# RS232_IrDA.net
KiCad netlist of a schematic drawn in Altium Designer
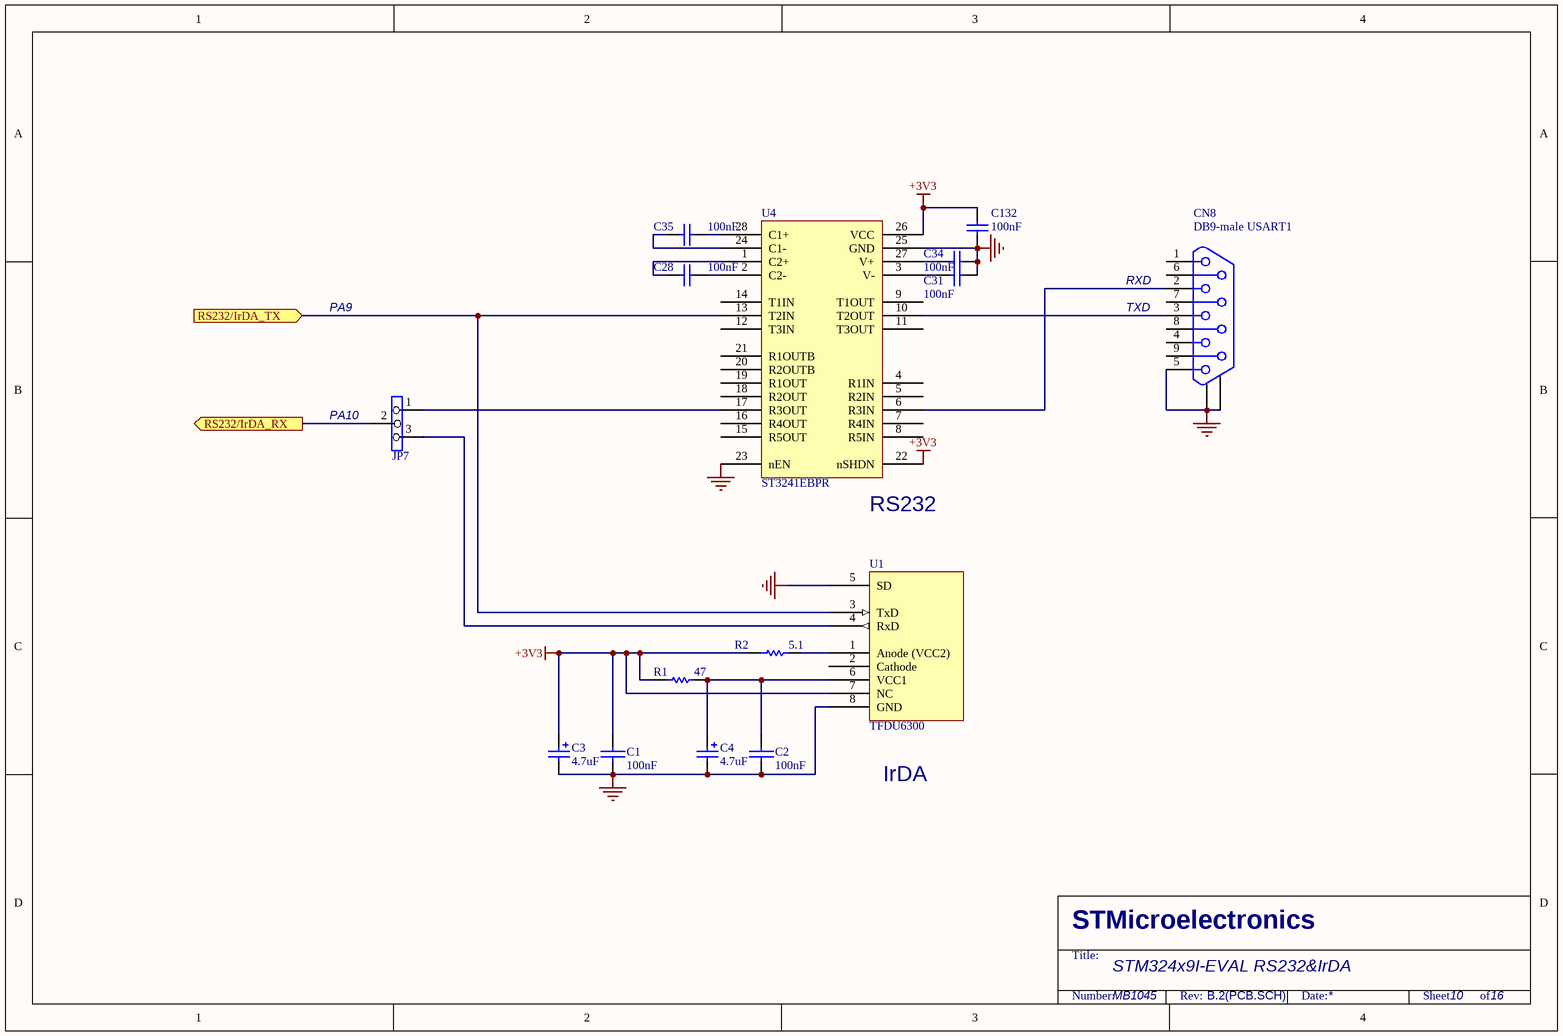
[diagram p0: RS232&IrDA.SchDoc]

(export (version "E")
  (design (tool "Eeschema 10.0.6"))
  (components
    (comp (ref "C1")
      (value "100nF")
      (footprint "0603C")
      (description "Capacitor")
      (libsource (lib "*") (part "CAP"))
    )
    (comp (ref "C2")
      (value "100nF")
      (footprint "0603C")
      (description "Capacitor")
      (libsource (lib "*") (part "CAP"))
    )
    (comp (ref "C3")
      (value "4.7uF")
      (footprint "TAN-A")
      (description "Polarized Capacitor (Radial)")
      (fields (field (name "PUBLISHER") "Altium Limited"))
      (libsource (lib "Miscellaneous Devices") (part "Cap Pol1"))
    )
    (comp (ref "C4")
      (value "4.7uF")
      (footprint "TAN-A")
      (description "Polarized Capacitor (Radial)")
      (fields (field (name "PUBLISHER") "Altium Limited"))
      (libsource (lib "Miscellaneous Devices") (part "Cap Pol1"))
    )
    (comp (ref "C28")
      (value "100nF")
      (footprint "0603C")
      (description "Capacitor")
      (fields (field (name "PUBLISHER") "Altium Limited"))
      (libsource (lib "Miscellaneous Devices") (part "Cap"))
    )
    (comp (ref "C31")
      (value "100nF")
      (footprint "0603C")
      (description "Capacitor")
      (fields (field (name "PUBLISHER") "Altium Limited"))
      (libsource (lib "Miscellaneous Devices") (part "Cap"))
    )
    (comp (ref "C34")
      (value "100nF")
      (footprint "0603C")
      (description "Capacitor")
      (fields (field (name "PUBLISHER") "Altium Limited"))
      (libsource (lib "Miscellaneous Devices") (part "Cap"))
    )
    (comp (ref "C35")
      (value "100nF")
      (footprint "0603C")
      (description "Capacitor")
      (fields (field (name "PUBLISHER") "Altium Limited"))
      (libsource (lib "Miscellaneous Devices") (part "Cap"))
    )
    (comp (ref "C132")
      (value "100nF")
      (footprint "0603C")
      (description "Capacitor")
      (fields (field (name "PUBLISHER") "Altium Limited"))
      (libsource (lib "Miscellaneous Devices") (part "Cap"))
    )
    (comp (ref "CN8")
      (value "DB9-male USART1")
      (footprint "DB9/M")
      (libsource (lib "mb1045") (part "DB9-USART"))
    )
    (comp (ref "JP7") (value "~") (footprint "SIP3") (libsource (lib "STR910_SCHLIB") (part "Jumper3")))
    (comp (ref "R1")
      (value "47")
      (footprint "0603R")
      (description "Resistor")
      (fields (field (name "PUBLISHER") "Altium Limited"))
      (libsource (lib "Miscellaneous Devices") (part "Res1"))
    )
    (comp (ref "R2")
      (value "5.1")
      (footprint "0603R")
      (description "Resistor")
      (fields (field (name "PUBLISHER") "Altium Limited"))
      (libsource (lib "Miscellaneous Devices") (part "Res1"))
    )
    (comp (ref "U1")
      (value "TFDU6300")
      (footprint "IR_VISHAY3")
      (description "TFDU4300")
      (libsource (lib "*") (part "TFDU4300"))
    )
    (comp (ref "U4")
      (value "ST3241EBPR")
      (footprint "SSOP28_0R65_10R2X7R8")
      (libsource (lib "*") (part "ST3241"))
    )
  )
  (nets
    (net (code "1") (name "+3V3") (class "Default")
      (node (ref "C1") (pin "1") (pinfunction "1_1") (pintype "passive"))
      (node (ref "C132") (pin "1") (pinfunction "1_1") (pintype "passive"))
      (node (ref "C3") (pin "1") (pinfunction "1_1") (pintype "passive"))
      (node (ref "R1") (pin "1") (pinfunction "1_1") (pintype "passive"))
      (node (ref "R2") (pin "1") (pinfunction "1_1") (pintype "passive"))
      (node (ref "U1") (pin "7") (pinfunction "NC_7") (pintype "passive"))
      (node (ref "U4") (pin "22") (pinfunction "nSHDN_22") (pintype "passive"))
      (node (ref "U4") (pin "26") (pinfunction "VCC_26") (pintype "passive"))
    )
    (net (code "2") (name "/RS232{slash}IrDA_RX") (class "Default")
      (node (ref "JP7") (pin "2") (pintype "passive"))
    )
    (net (code "3") (name "/RS232{slash}IrDA_TX") (class "Default")
      (node (ref "U1") (pin "3") (pinfunction "TxD_3") (pintype "input"))
      (node (ref "U4") (pin "13") (pinfunction "T2IN_13") (pintype "passive"))
    )
    (net (code "4") (name "GND") (class "Default")
      (node (ref "C1") (pin "2") (pinfunction "2_2") (pintype "passive"))
      (node (ref "C132") (pin "2") (pinfunction "2_2") (pintype "passive"))
      (node (ref "C2") (pin "2") (pinfunction "2_2") (pintype "passive"))
      (node (ref "C3") (pin "2") (pinfunction "2_2") (pintype "passive"))
      (node (ref "C31") (pin "1") (pinfunction "1_1") (pintype "passive"))
      (node (ref "C34") (pin "1") (pinfunction "1_1") (pintype "passive"))
      (node (ref "C4") (pin "2") (pinfunction "2_2") (pintype "passive"))
      (node (ref "CN8") (pin "10") (pinfunction "10_10") (pintype "passive"))
      (node (ref "CN8") (pin "11") (pinfunction "11_11") (pintype "passive"))
      (node (ref "CN8") (pin "5") (pinfunction "5_5") (pintype "passive"))
      (node (ref "U1") (pin "5") (pinfunction "SD_5") (pintype "passive"))
      (node (ref "U1") (pin "8") (pinfunction "GND_8") (pintype "passive"))
      (node (ref "U4") (pin "23") (pinfunction "nEN_23") (pintype "passive"))
      (node (ref "U4") (pin "25") (pinfunction "GND_25") (pintype "passive"))
    )
    (net (code "5") (name "Net-(U1-Anode_(VCC2))") (class "Default")
      (node (ref "R2") (pin "2") (pinfunction "2_2") (pintype "passive"))
      (node (ref "U1") (pin "1") (pinfunction "Anode_(VCC2)_1") (pintype "passive"))
    )
    (net (code "6") (name "Net-(U1-RxD)") (class "Default")
      (node (ref "JP7") (pin "3") (pintype "passive"))
      (node (ref "U1") (pin "4") (pinfunction "RxD_4") (pintype "output"))
    )
    (net (code "7") (name "Net-(U1-VCC1)") (class "Default")
      (node (ref "C2") (pin "1") (pinfunction "1_1") (pintype "passive"))
      (node (ref "C4") (pin "1") (pinfunction "1_1") (pintype "passive"))
      (node (ref "R1") (pin "2") (pinfunction "2_2") (pintype "passive"))
      (node (ref "U1") (pin "6") (pinfunction "VCC1_6") (pintype "passive"))
    )
    (net (code "8") (name "Net-(U4-C1+)") (class "Default")
      (node (ref "C35") (pin "2") (pinfunction "2_2") (pintype "passive"))
      (node (ref "U4") (pin "28") (pinfunction "C1+_28") (pintype "passive"))
    )
    (net (code "9") (name "Net-(U4-C1-)") (class "Default")
      (node (ref "C35") (pin "1") (pinfunction "1_1") (pintype "passive"))
      (node (ref "U4") (pin "24") (pinfunction "C1-_24") (pintype "passive"))
    )
    (net (code "10") (name "Net-(U4-C2+)") (class "Default")
      (node (ref "C28") (pin "1") (pinfunction "1_1") (pintype "passive"))
      (node (ref "U4") (pin "1") (pinfunction "C2+_1") (pintype "passive"))
    )
    (net (code "11") (name "Net-(U4-C2-)") (class "Default")
      (node (ref "C28") (pin "2") (pinfunction "2_2") (pintype "passive"))
      (node (ref "U4") (pin "2") (pinfunction "C2-_2") (pintype "passive"))
    )
    (net (code "12") (name "Net-(U4-R3IN)") (class "Default")
      (node (ref "CN8") (pin "2") (pinfunction "2_2") (pintype "passive"))
      (node (ref "U4") (pin "6") (pinfunction "R3IN_6") (pintype "passive"))
    )
    (net (code "13") (name "Net-(U4-R3OUT)") (class "Default")
      (node (ref "JP7") (pin "1") (pintype "passive"))
      (node (ref "U4") (pin "17") (pinfunction "R3OUT_17") (pintype "passive"))
    )
    (net (code "14") (name "Net-(U4-T2OUT)") (class "Default")
      (node (ref "CN8") (pin "3") (pinfunction "3_3") (pintype "passive"))
      (node (ref "U4") (pin "10") (pinfunction "T2OUT_10") (pintype "passive"))
    )
    (net (code "15") (name "Net-(U4-V+)") (class "Default")
      (node (ref "C34") (pin "2") (pinfunction "2_2") (pintype "passive"))
      (node (ref "U4") (pin "27") (pinfunction "V+_27") (pintype "passive"))
    )
    (net (code "16") (name "Net-(U4-V-)") (class "Default")
      (node (ref "C31") (pin "2") (pinfunction "2_2") (pintype "passive"))
      (node (ref "U4") (pin "3") (pinfunction "V-_3") (pintype "passive"))
    )
    (net (code "17") (name "unconnected-(CN8-Pad1)") (class "Default")
      (node (ref "CN8") (pin "1") (pinfunction "1_1") (pintype "passive"))
    )
    (net (code "18") (name "unconnected-(CN8-Pad4)") (class "Default")
      (node (ref "CN8") (pin "4") (pinfunction "4_4") (pintype "passive"))
    )
    (net (code "19") (name "unconnected-(CN8-Pad6)") (class "Default")
      (node (ref "CN8") (pin "6") (pinfunction "6_6") (pintype "passive"))
    )
    (net (code "20") (name "unconnected-(CN8-Pad7)") (class "Default")
      (node (ref "CN8") (pin "7") (pinfunction "7_7") (pintype "passive"))
    )
    (net (code "21") (name "unconnected-(CN8-Pad8)") (class "Default")
      (node (ref "CN8") (pin "8") (pinfunction "8_8") (pintype "passive"))
    )
    (net (code "22") (name "unconnected-(CN8-Pad9)") (class "Default")
      (node (ref "CN8") (pin "9") (pinfunction "9_9") (pintype "passive"))
    )
    (net (code "23") (name "unconnected-(U1-Cathode-Pad2)") (class "Default")
      (node (ref "U1") (pin "2") (pinfunction "Cathode_2") (pintype "passive"))
    )
    (net (code "24") (name "unconnected-(U4-R1IN-Pad4)") (class "Default")
      (node (ref "U4") (pin "4") (pinfunction "R1IN_4") (pintype "passive"))
    )
    (net (code "25") (name "unconnected-(U4-R1OUT-Pad19)") (class "Default")
      (node (ref "U4") (pin "19") (pinfunction "R1OUT_19") (pintype "passive"))
    )
    (net (code "26") (name "unconnected-(U4-R1OUTB-Pad21)") (class "Default")
      (node (ref "U4") (pin "21") (pinfunction "R1OUTB_21") (pintype "passive"))
    )
    (net (code "27") (name "unconnected-(U4-R2IN-Pad5)") (class "Default")
      (node (ref "U4") (pin "5") (pinfunction "R2IN_5") (pintype "passive"))
    )
    (net (code "28") (name "unconnected-(U4-R2OUT-Pad18)") (class "Default")
      (node (ref "U4") (pin "18") (pinfunction "R2OUT_18") (pintype "passive"))
    )
    (net (code "29") (name "unconnected-(U4-R2OUTB-Pad20)") (class "Default")
      (node (ref "U4") (pin "20") (pinfunction "R2OUTB_20") (pintype "passive"))
    )
    (net (code "30") (name "unconnected-(U4-R4IN-Pad7)") (class "Default")
      (node (ref "U4") (pin "7") (pinfunction "R4IN_7") (pintype "passive"))
    )
    (net (code "31") (name "unconnected-(U4-R4OUT-Pad16)") (class "Default")
      (node (ref "U4") (pin "16") (pinfunction "R4OUT_16") (pintype "passive"))
    )
    (net (code "32") (name "unconnected-(U4-R5IN-Pad8)") (class "Default")
      (node (ref "U4") (pin "8") (pinfunction "R5IN_8") (pintype "passive"))
    )
    (net (code "33") (name "unconnected-(U4-R5OUT-Pad15)") (class "Default")
      (node (ref "U4") (pin "15") (pinfunction "R5OUT_15") (pintype "passive"))
    )
    (net (code "34") (name "unconnected-(U4-T1IN-Pad14)") (class "Default")
      (node (ref "U4") (pin "14") (pinfunction "T1IN_14") (pintype "passive"))
    )
    (net (code "35") (name "unconnected-(U4-T1OUT-Pad9)") (class "Default")
      (node (ref "U4") (pin "9") (pinfunction "T1OUT_9") (pintype "passive"))
    )
    (net (code "36") (name "unconnected-(U4-T3IN-Pad12)") (class "Default")
      (node (ref "U4") (pin "12") (pinfunction "T3IN_12") (pintype "passive"))
    )
    (net (code "37") (name "unconnected-(U4-T3OUT-Pad11)") (class "Default")
      (node (ref "U4") (pin "11") (pinfunction "T3OUT_11") (pintype "passive"))
    )
  )
)
